# Pr_tica-09.net
KiCad netlist of a schematic drawn in EasyEDA
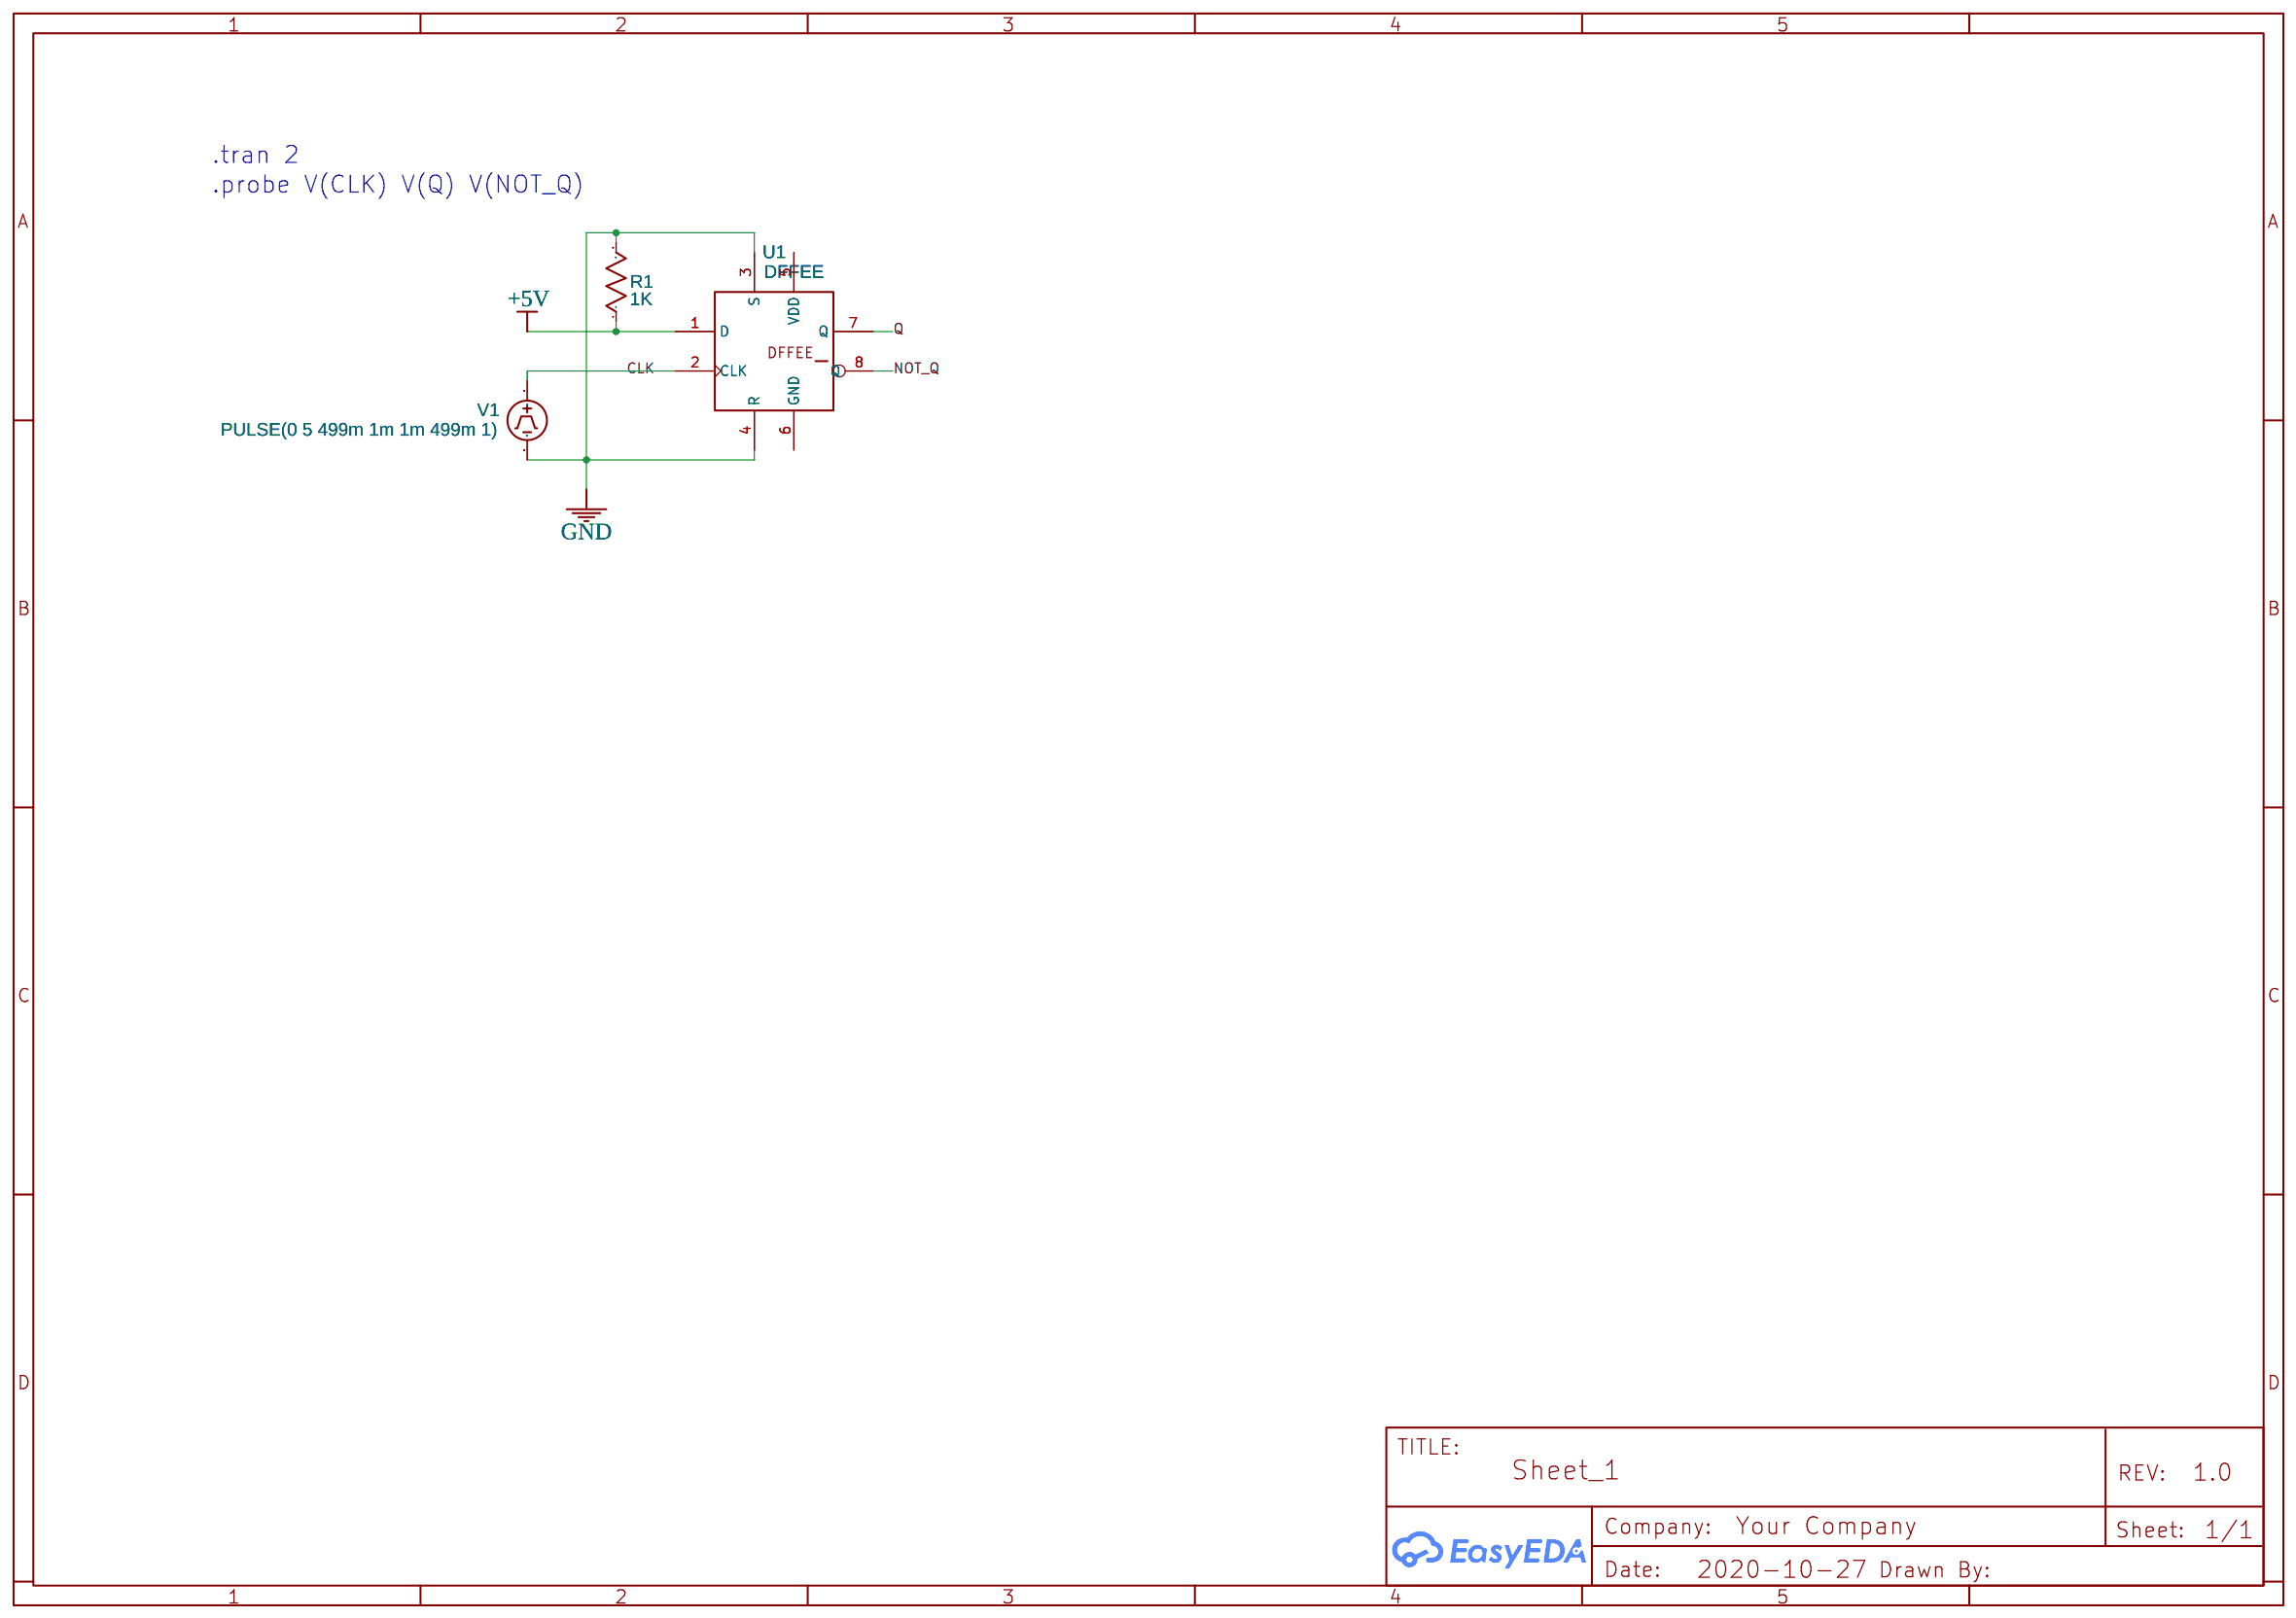
[diagram p0: schematic sheet]

(export (version "E")
  (design (tool "Eeschema 10.0.6"))
  (components
    (comp (ref "R1") (value "1K") (libsource (lib "") (part "Resistor_US")))
    (comp (ref "U1") (value "DFFEE") (libsource (lib "") (part "LOGIC")))
    (comp (ref "V1") (value "PULSE(0 5 499m 1m 1m 499m 1)") (libsource (lib "") (part "VPULSE")))
  )
  (nets
    (net (code "1") (name "+5V") (class "Default")
      (node (ref "R1") (pin "1") (pinfunction "1_1") (pintype "unspecified"))
      (node (ref "U1") (pin "1") (pinfunction "D_1") (pintype "unspecified"))
    )
    (net (code "2") (name "/CLK") (class "Default")
      (node (ref "U1") (pin "2") (pinfunction "CLK_2") (pintype "unspecified"))
      (node (ref "V1") (pin "1") (pinfunction "1_1") (pintype "unspecified"))
    )
    (net (code "3") (name "/NOT_Q") (class "Default")
      (node (ref "U1") (pin "8") (pinfunction "Q_8") (pintype "unspecified"))
    )
    (net (code "4") (name "/Q") (class "Default")
      (node (ref "U1") (pin "7") (pinfunction "Q_7") (pintype "unspecified"))
    )
    (net (code "5") (name "GND") (class "Default")
      (node (ref "R1") (pin "2") (pinfunction "2_2") (pintype "unspecified"))
      (node (ref "U1") (pin "3") (pinfunction "S_3") (pintype "unspecified"))
      (node (ref "U1") (pin "4") (pinfunction "R_4") (pintype "unspecified"))
      (node (ref "V1") (pin "2") (pinfunction "2_2") (pintype "unspecified"))
    )
    (net (code "6") (name "unconnected-(U1-GND-Pad6)") (class "Default")
      (node (ref "U1") (pin "6") (pinfunction "GND_6") (pintype "unspecified"))
    )
    (net (code "7") (name "unconnected-(U1-VDD-Pad5)") (class "Default")
      (node (ref "U1") (pin "5") (pinfunction "VDD_5") (pintype "unspecified"))
    )
  )
)
